# Sheet1_GMAX0505_MEZ.net
KiCad netlist of a schematic drawn in Altium Designer
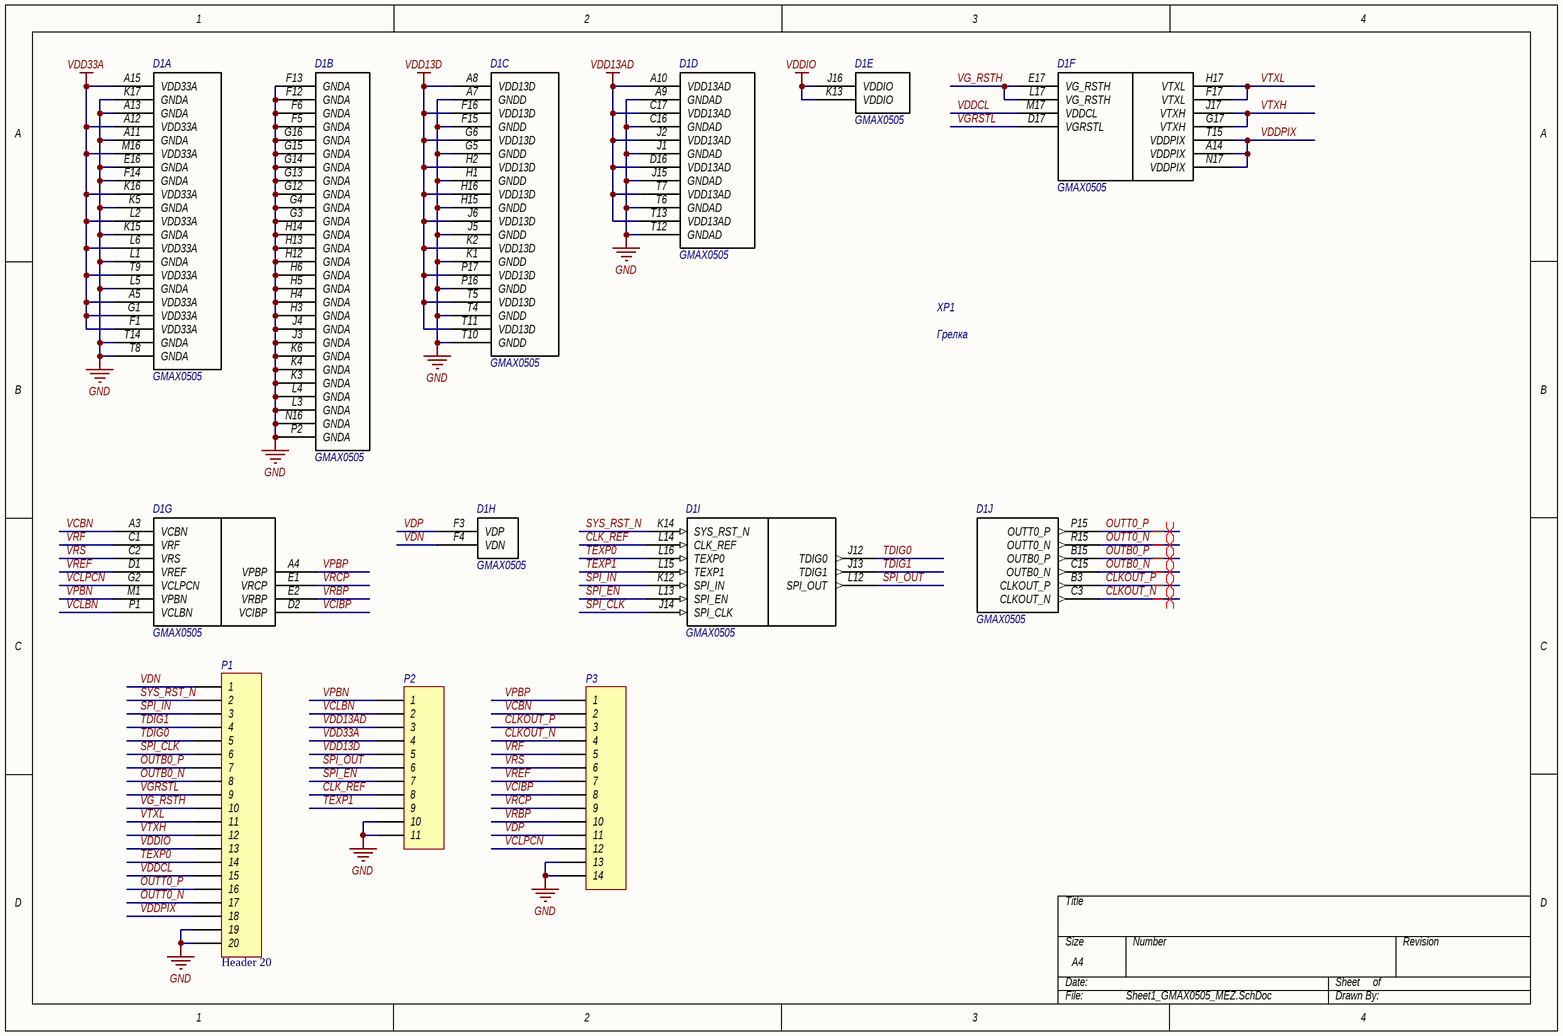
[diagram p0: Sheet1_GMAX0505_MEZ.SchDoc]

(export (version "E")
  (design (tool "Eeschema 10.0.6"))
  (components
    (comp (ref "D1") (value "GMAX0505") (footprint "GMAX0505") (libsource (lib "Schlib") (part "GMAX0505")))
    (comp (ref "P1")
      (value "Header 20")
      (footprint "HDR1X20")
      (description "Header, 20-Pin")
      (fields (field (name "PUBLISHER") "Altium Limited"))
      (libsource (lib "Miscellaneous Connectors") (part "Header 20"))
    )
    (comp (ref "P2")
      (value "Header 11")
      (footprint "HDR1X11")
      (description "Header, 11-Pin")
      (fields (field (name "PUBLISHER") "Altium Limited"))
      (libsource (lib "Miscellaneous Connectors") (part "Header 11"))
    )
    (comp (ref "P3")
      (value "Header 14")
      (footprint "HDR1X14")
      (description "Header, 14-Pin")
      (fields (field (name "PUBLISHER") "Altium Limited"))
      (libsource (lib "Miscellaneous Connectors") (part "Header 14"))
    )
    (comp (ref "XP1") (value "Грелка") (footprint "Грелка") (libsource (lib "VPL") (part "Грелка")))
  )
  (nets
    (net (code "1") (name "/CLKOUT_N") (class "Default")
      (node (ref "D1") (pin "C3") (pinfunction "CLKOUT_N_C3") (pintype "output"))
      (node (ref "P3") (pin "4") (pinfunction "4_4") (pintype "passive"))
    )
    (net (code "2") (name "/CLKOUT_P") (class "Default")
      (node (ref "D1") (pin "B3") (pinfunction "CLKOUT_P_B3") (pintype "output"))
      (node (ref "P3") (pin "3") (pinfunction "3_3") (pintype "passive"))
    )
    (net (code "3") (name "/CLK_REF") (class "Default")
      (node (ref "D1") (pin "L14") (pinfunction "CLK_REF_L14") (pintype "input"))
      (node (ref "P2") (pin "8") (pinfunction "8_8") (pintype "passive"))
    )
    (net (code "4") (name "/OUTB0_N") (class "Default")
      (node (ref "D1") (pin "C15") (pinfunction "OUTB0_N_C15") (pintype "output"))
      (node (ref "P1") (pin "8") (pinfunction "8_8") (pintype "passive"))
    )
    (net (code "5") (name "/OUTB0_P") (class "Default")
      (node (ref "D1") (pin "B15") (pinfunction "OUTB0_P_B15") (pintype "output"))
      (node (ref "P1") (pin "7") (pinfunction "7_7") (pintype "passive"))
    )
    (net (code "6") (name "/OUTT0_N") (class "Default")
      (node (ref "D1") (pin "R15") (pinfunction "OUTT0_N_R15") (pintype "output"))
      (node (ref "P1") (pin "17") (pinfunction "17_17") (pintype "passive"))
    )
    (net (code "7") (name "/OUTT0_P") (class "Default")
      (node (ref "D1") (pin "P15") (pinfunction "OUTT0_P_P15") (pintype "output"))
      (node (ref "P1") (pin "16") (pinfunction "16_16") (pintype "passive"))
    )
    (net (code "8") (name "/SPI_CLK") (class "Default")
      (node (ref "D1") (pin "J14") (pinfunction "SPI_CLK_J14") (pintype "input"))
      (node (ref "P1") (pin "6") (pinfunction "6_6") (pintype "passive"))
    )
    (net (code "9") (name "/SPI_EN") (class "Default")
      (node (ref "D1") (pin "L13") (pinfunction "SPI_EN_L13") (pintype "input"))
      (node (ref "P2") (pin "7") (pinfunction "7_7") (pintype "passive"))
    )
    (net (code "10") (name "/SPI_IN") (class "Default")
      (node (ref "D1") (pin "K12") (pinfunction "SPI_IN_K12") (pintype "input"))
      (node (ref "P1") (pin "3") (pinfunction "3_3") (pintype "passive"))
    )
    (net (code "11") (name "/SPI_OUT") (class "Default")
      (node (ref "D1") (pin "L12") (pinfunction "SPI_OUT_L12") (pintype "output"))
      (node (ref "P2") (pin "6") (pinfunction "6_6") (pintype "passive"))
    )
    (net (code "12") (name "/SYS_RST_N") (class "Default")
      (node (ref "D1") (pin "K14") (pinfunction "SYS_RST_N_K14") (pintype "input"))
      (node (ref "P1") (pin "2") (pinfunction "2_2") (pintype "passive"))
    )
    (net (code "13") (name "/TDIG0") (class "Default")
      (node (ref "D1") (pin "J12") (pinfunction "TDIG0_J12") (pintype "output"))
      (node (ref "P1") (pin "5") (pinfunction "5_5") (pintype "passive"))
    )
    (net (code "14") (name "/TDIG1") (class "Default")
      (node (ref "D1") (pin "J13") (pinfunction "TDIG1_J13") (pintype "output"))
      (node (ref "P1") (pin "4") (pinfunction "4_4") (pintype "passive"))
    )
    (net (code "15") (name "/TEXP0") (class "Default")
      (node (ref "D1") (pin "L16") (pinfunction "TEXP0_L16") (pintype "input"))
      (node (ref "P1") (pin "14") (pinfunction "14_14") (pintype "passive"))
    )
    (net (code "16") (name "/TEXP1") (class "Default")
      (node (ref "D1") (pin "L15") (pinfunction "TEXP1_L15") (pintype "input"))
      (node (ref "P2") (pin "9") (pinfunction "9_9") (pintype "passive"))
    )
    (net (code "17") (name "/VCBN") (class "Default")
      (node (ref "D1") (pin "A3") (pinfunction "VCBN_A3") (pintype "passive"))
      (node (ref "P3") (pin "2") (pinfunction "2_2") (pintype "passive"))
    )
    (net (code "18") (name "/VCIBP") (class "Default")
      (node (ref "D1") (pin "D2") (pinfunction "VCIBP_D2") (pintype "passive"))
      (node (ref "P3") (pin "8") (pinfunction "8_8") (pintype "passive"))
    )
    (net (code "19") (name "/VCLBN") (class "Default")
      (node (ref "D1") (pin "P1") (pinfunction "VCLBN_P1") (pintype "passive"))
      (node (ref "P2") (pin "2") (pinfunction "2_2") (pintype "passive"))
    )
    (net (code "20") (name "/VCLPCN") (class "Default")
      (node (ref "D1") (pin "G2") (pinfunction "VCLPCN_G2") (pintype "passive"))
      (node (ref "P3") (pin "12") (pinfunction "12_12") (pintype "passive"))
    )
    (net (code "21") (name "/VDDCL") (class "Default")
      (node (ref "D1") (pin "M17") (pinfunction "VDDCL_M17") (pintype "passive"))
      (node (ref "P1") (pin "15") (pinfunction "15_15") (pintype "passive"))
    )
    (net (code "22") (name "/VDDPIX") (class "Default")
      (node (ref "D1") (pin "A14") (pinfunction "VDDPIX_A14") (pintype "passive"))
      (node (ref "D1") (pin "N17") (pinfunction "VDDPIX_N17") (pintype "passive"))
      (node (ref "D1") (pin "T15") (pinfunction "VDDPIX_T15") (pintype "passive"))
      (node (ref "P1") (pin "18") (pinfunction "18_18") (pintype "passive"))
    )
    (net (code "23") (name "/VDN") (class "Default")
      (node (ref "D1") (pin "F4") (pinfunction "VDN_F4") (pintype "passive"))
      (node (ref "P1") (pin "1") (pinfunction "1_1") (pintype "passive"))
    )
    (net (code "24") (name "/VDP") (class "Default")
      (node (ref "D1") (pin "F3") (pinfunction "VDP_F3") (pintype "passive"))
      (node (ref "P3") (pin "11") (pinfunction "11_11") (pintype "passive"))
    )
    (net (code "25") (name "/VGRSTL") (class "Default")
      (node (ref "D1") (pin "D17") (pinfunction "VGRSTL_D17") (pintype "passive"))
      (node (ref "P1") (pin "9") (pinfunction "9_9") (pintype "passive"))
    )
    (net (code "26") (name "/VG_RSTH") (class "Default")
      (node (ref "D1") (pin "E17") (pinfunction "VG_RSTH_E17") (pintype "passive"))
      (node (ref "D1") (pin "L17") (pinfunction "VG_RSTH_L17") (pintype "passive"))
      (node (ref "P1") (pin "10") (pinfunction "10_10") (pintype "passive"))
    )
    (net (code "27") (name "/VPBN") (class "Default")
      (node (ref "D1") (pin "M1") (pinfunction "VPBN_M1") (pintype "passive"))
      (node (ref "P2") (pin "1") (pinfunction "1_1") (pintype "passive"))
    )
    (net (code "28") (name "/VPBP") (class "Default")
      (node (ref "D1") (pin "A4") (pinfunction "VPBP_A4") (pintype "passive"))
      (node (ref "P3") (pin "1") (pinfunction "1_1") (pintype "passive"))
    )
    (net (code "29") (name "/VRBP") (class "Default")
      (node (ref "D1") (pin "E2") (pinfunction "VRBP_E2") (pintype "passive"))
      (node (ref "P3") (pin "10") (pinfunction "10_10") (pintype "passive"))
    )
    (net (code "30") (name "/VRCP") (class "Default")
      (node (ref "D1") (pin "E1") (pinfunction "VRCP_E1") (pintype "passive"))
      (node (ref "P3") (pin "9") (pinfunction "9_9") (pintype "passive"))
    )
    (net (code "31") (name "/VREF") (class "Default")
      (node (ref "D1") (pin "D1") (pinfunction "VREF_D1") (pintype "passive"))
      (node (ref "P3") (pin "7") (pinfunction "7_7") (pintype "passive"))
    )
    (net (code "32") (name "/VRF") (class "Default")
      (node (ref "D1") (pin "C1") (pinfunction "VRF_C1") (pintype "passive"))
      (node (ref "P3") (pin "5") (pinfunction "5_5") (pintype "passive"))
    )
    (net (code "33") (name "/VRS") (class "Default")
      (node (ref "D1") (pin "C2") (pinfunction "VRS_C2") (pintype "passive"))
      (node (ref "P3") (pin "6") (pinfunction "6_6") (pintype "passive"))
    )
    (net (code "34") (name "/VTXH") (class "Default")
      (node (ref "D1") (pin "G17") (pinfunction "VTXH_G17") (pintype "passive"))
      (node (ref "D1") (pin "J17") (pinfunction "VTXH_J17") (pintype "passive"))
      (node (ref "P1") (pin "12") (pinfunction "12_12") (pintype "passive"))
    )
    (net (code "35") (name "/VTXL") (class "Default")
      (node (ref "D1") (pin "F17") (pinfunction "VTXL_F17") (pintype "passive"))
      (node (ref "D1") (pin "H17") (pinfunction "VTXL_H17") (pintype "passive"))
      (node (ref "P1") (pin "11") (pinfunction "11_11") (pintype "passive"))
    )
    (net (code "36") (name "GND") (class "Default")
      (node (ref "D1") (pin "A11") (pinfunction "GNDA_A11") (pintype "passive"))
      (node (ref "D1") (pin "A13") (pinfunction "GNDA_A13") (pintype "passive"))
      (node (ref "D1") (pin "A7") (pinfunction "GNDD_A7") (pintype "passive"))
      (node (ref "D1") (pin "A9") (pinfunction "GNDAD_A9") (pintype "passive"))
      (node (ref "D1") (pin "C16") (pinfunction "GNDAD_C16") (pintype "passive"))
      (node (ref "D1") (pin "E16") (pinfunction "GNDA_E16") (pintype "passive"))
      (node (ref "D1") (pin "F12") (pinfunction "GNDA_F12") (pintype "passive"))
      (node (ref "D1") (pin "F13") (pinfunction "GNDA_F13") (pintype "passive"))
      (node (ref "D1") (pin "F14") (pinfunction "GNDA_F14") (pintype "passive"))
      (node (ref "D1") (pin "F15") (pinfunction "GNDD_F15") (pintype "passive"))
      (node (ref "D1") (pin "F5") (pinfunction "GNDA_F5") (pintype "passive"))
      (node (ref "D1") (pin "F6") (pinfunction "GNDA_F6") (pintype "passive"))
      (node (ref "D1") (pin "G12") (pinfunction "GNDA_G12") (pintype "passive"))
      (node (ref "D1") (pin "G13") (pinfunction "GNDA_G13") (pintype "passive"))
      (node (ref "D1") (pin "G14") (pinfunction "GNDA_G14") (pintype "passive"))
      (node (ref "D1") (pin "G15") (pinfunction "GNDA_G15") (pintype "passive"))
      (node (ref "D1") (pin "G16") (pinfunction "GNDA_G16") (pintype "passive"))
      (node (ref "D1") (pin "G3") (pinfunction "GNDA_G3") (pintype "passive"))
      (node (ref "D1") (pin "G4") (pinfunction "GNDA_G4") (pintype "passive"))
      (node (ref "D1") (pin "G5") (pinfunction "GNDD_G5") (pintype "passive"))
      (node (ref "D1") (pin "H1") (pinfunction "GNDD_H1") (pintype "passive"))
      (node (ref "D1") (pin "H12") (pinfunction "GNDA_H12") (pintype "passive"))
      (node (ref "D1") (pin "H13") (pinfunction "GNDA_H13") (pintype "passive"))
      (node (ref "D1") (pin "H14") (pinfunction "GNDA_H14") (pintype "passive"))
      (node (ref "D1") (pin "H15") (pinfunction "GNDD_H15") (pintype "passive"))
      (node (ref "D1") (pin "H3") (pinfunction "GNDA_H3") (pintype "passive"))
      (node (ref "D1") (pin "H4") (pinfunction "GNDA_H4") (pintype "passive"))
      (node (ref "D1") (pin "H5") (pinfunction "GNDA_H5") (pintype "passive"))
      (node (ref "D1") (pin "H6") (pinfunction "GNDA_H6") (pintype "passive"))
      (node (ref "D1") (pin "J1") (pinfunction "GNDAD_J1") (pintype "passive"))
      (node (ref "D1") (pin "J15") (pinfunction "GNDAD_J15") (pintype "passive"))
      (node (ref "D1") (pin "J3") (pinfunction "GNDA_J3") (pintype "passive"))
      (node (ref "D1") (pin "J4") (pinfunction "GNDA_J4") (pintype "passive"))
      (node (ref "D1") (pin "J5") (pinfunction "GNDD_J5") (pintype "passive"))
      (node (ref "D1") (pin "K1") (pinfunction "GNDD_K1") (pintype "passive"))
      (node (ref "D1") (pin "K15") (pinfunction "GNDA_K15") (pintype "passive"))
      (node (ref "D1") (pin "K17") (pinfunction "GNDA_K17") (pintype "passive"))
      (node (ref "D1") (pin "K3") (pinfunction "GNDA_K3") (pintype "passive"))
      (node (ref "D1") (pin "K4") (pinfunction "GNDA_K4") (pintype "passive"))
      (node (ref "D1") (pin "K5") (pinfunction "GNDA_K5") (pintype "passive"))
      (node (ref "D1") (pin "K6") (pinfunction "GNDA_K6") (pintype "passive"))
      (node (ref "D1") (pin "L1") (pinfunction "GNDA_L1") (pintype "passive"))
      (node (ref "D1") (pin "L3") (pinfunction "GNDA_L3") (pintype "passive"))
      (node (ref "D1") (pin "L4") (pinfunction "GNDA_L4") (pintype "passive"))
      (node (ref "D1") (pin "L5") (pinfunction "GNDA_L5") (pintype "passive"))
      (node (ref "D1") (pin "N16") (pinfunction "GNDA_N16") (pintype "passive"))
      (node (ref "D1") (pin "P16") (pinfunction "GNDD_P16") (pintype "passive"))
      (node (ref "D1") (pin "P2") (pinfunction "GNDA_P2") (pintype "passive"))
      (node (ref "D1") (pin "T10") (pinfunction "GNDD_T10") (pintype "passive"))
      (node (ref "D1") (pin "T12") (pinfunction "GNDAD_T12") (pintype "passive"))
      (node (ref "D1") (pin "T14") (pinfunction "GNDA_T14") (pintype "passive"))
      (node (ref "D1") (pin "T4") (pinfunction "GNDD_T4") (pintype "passive"))
      (node (ref "D1") (pin "T6") (pinfunction "GNDAD_T6") (pintype "passive"))
      (node (ref "D1") (pin "T8") (pinfunction "GNDA_T8") (pintype "passive"))
      (node (ref "P1") (pin "19") (pinfunction "19_19") (pintype "passive"))
      (node (ref "P1") (pin "20") (pinfunction "20_20") (pintype "passive"))
      (node (ref "P2") (pin "10") (pinfunction "10_10") (pintype "passive"))
      (node (ref "P2") (pin "11") (pinfunction "11_11") (pintype "passive"))
      (node (ref "P3") (pin "13") (pinfunction "13_13") (pintype "passive"))
      (node (ref "P3") (pin "14") (pinfunction "14_14") (pintype "passive"))
    )
    (net (code "37") (name "VDD13AD") (class "Default")
      (node (ref "D1") (pin "A10") (pinfunction "VDD13AD_A10") (pintype "passive"))
      (node (ref "D1") (pin "C17") (pinfunction "VDD13AD_C17") (pintype "passive"))
      (node (ref "D1") (pin "D16") (pinfunction "VDD13AD_D16") (pintype "passive"))
      (node (ref "D1") (pin "J2") (pinfunction "VDD13AD_J2") (pintype "passive"))
      (node (ref "D1") (pin "T13") (pinfunction "VDD13AD_T13") (pintype "passive"))
      (node (ref "D1") (pin "T7") (pinfunction "VDD13AD_T7") (pintype "passive"))
      (node (ref "P2") (pin "3") (pinfunction "3_3") (pintype "passive"))
    )
    (net (code "38") (name "VDD13D") (class "Default")
      (node (ref "D1") (pin "A8") (pinfunction "VDD13D_A8") (pintype "passive"))
      (node (ref "D1") (pin "F16") (pinfunction "VDD13D_F16") (pintype "passive"))
      (node (ref "D1") (pin "G6") (pinfunction "VDD13D_G6") (pintype "passive"))
      (node (ref "D1") (pin "H16") (pinfunction "VDD13D_H16") (pintype "passive"))
      (node (ref "D1") (pin "H2") (pinfunction "VDD13D_H2") (pintype "passive"))
      (node (ref "D1") (pin "J6") (pinfunction "VDD13D_J6") (pintype "passive"))
      (node (ref "D1") (pin "K2") (pinfunction "VDD13D_K2") (pintype "passive"))
      (node (ref "D1") (pin "P17") (pinfunction "VDD13D_P17") (pintype "passive"))
      (node (ref "D1") (pin "T11") (pinfunction "VDD13D_T11") (pintype "passive"))
      (node (ref "D1") (pin "T5") (pinfunction "VDD13D_T5") (pintype "passive"))
      (node (ref "P2") (pin "5") (pinfunction "5_5") (pintype "passive"))
    )
    (net (code "39") (name "VDD33A") (class "Default")
      (node (ref "D1") (pin "A12") (pinfunction "VDD33A_A12") (pintype "passive"))
      (node (ref "D1") (pin "A15") (pinfunction "VDD33A_A15") (pintype "passive"))
      (node (ref "D1") (pin "A5") (pinfunction "VDD33A_A5") (pintype "passive"))
      (node (ref "D1") (pin "F1") (pinfunction "VDD33A_F1") (pintype "passive"))
      (node (ref "D1") (pin "G1") (pinfunction "VDD33A_G1") (pintype "passive"))
      (node (ref "D1") (pin "K16") (pinfunction "VDD33A_K16") (pintype "passive"))
      (node (ref "D1") (pin "L2") (pinfunction "VDD33A_L2") (pintype "passive"))
      (node (ref "D1") (pin "L6") (pinfunction "VDD33A_L6") (pintype "passive"))
      (node (ref "D1") (pin "M16") (pinfunction "VDD33A_M16") (pintype "passive"))
      (node (ref "D1") (pin "T9") (pinfunction "VDD33A_T9") (pintype "passive"))
      (node (ref "P2") (pin "4") (pinfunction "4_4") (pintype "passive"))
    )
    (net (code "40") (name "VDDIO") (class "Default")
      (node (ref "D1") (pin "J16") (pinfunction "VDDIO_J16") (pintype "passive"))
      (node (ref "D1") (pin "K13") (pinfunction "VDDIO_K13") (pintype "passive"))
      (node (ref "P1") (pin "13") (pinfunction "13_13") (pintype "passive"))
    )
  )
)
